# Extender.net
KiCad netlist of a schematic drawn in EAGLE
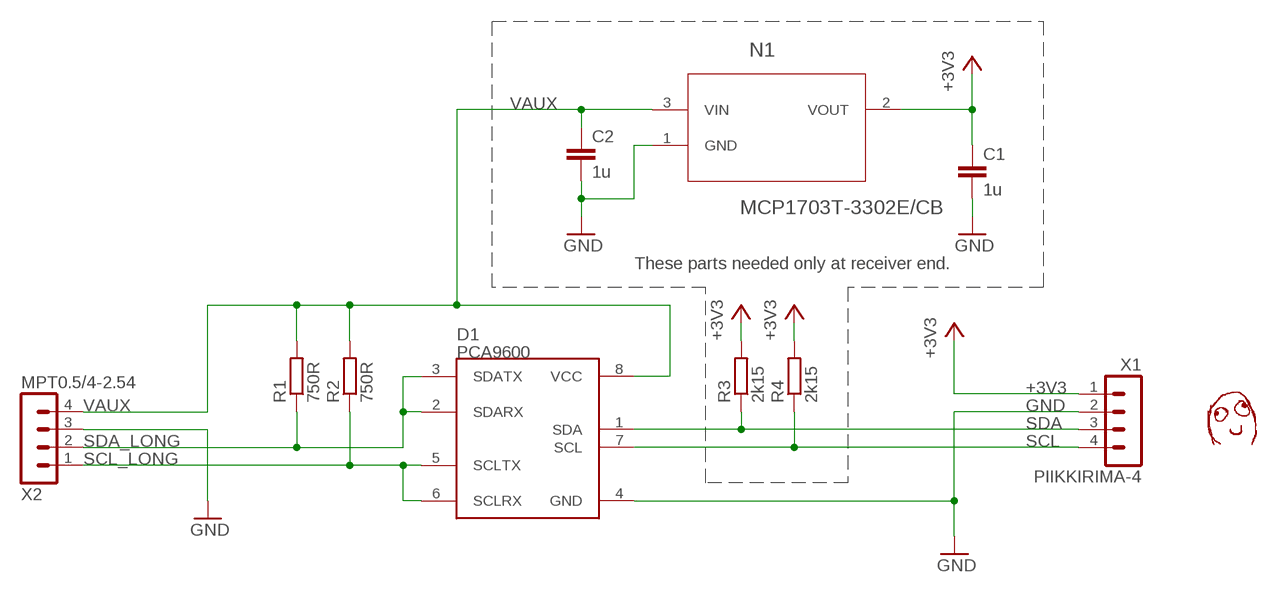
[diagram p0: schematic, sheet 1]

(export (version "E")
  (design (tool "Eeschema 10.0.6"))
  (components
    (comp (ref "C1")
      (value "1u")
      (footprint "eagle-import:C0805")
      (libsource (lib "eagle-import") (part "C-EUC0805"))
    )
    (comp (ref "C2")
      (value "1u")
      (footprint "eagle-import:C0805")
      (libsource (lib "eagle-import") (part "C-EUC0805"))
    )
    (comp (ref "D1")
      (value "PCA9600")
      (footprint "eagle-import:SOP65P490X110-8N")
      (libsource (lib "eagle-import") (part "PCA9600"))
    )
    (comp (ref "N1")
      (value "MCP1703T-3302E/CB")
      (footprint "eagle-import:SOT95P300X145-3N")
      (libsource (lib "eagle-import") (part "MCP1703T-3302E/CB"))
    )
    (comp (ref "R1")
      (value "750R")
      (footprint "eagle-import:R0603")
      (libsource (lib "eagle-import") (part "R-EU_R0603"))
    )
    (comp (ref "R2")
      (value "750R")
      (footprint "eagle-import:R0603")
      (libsource (lib "eagle-import") (part "R-EU_R0603"))
    )
    (comp (ref "R3")
      (value "2k15")
      (footprint "eagle-import:R0603")
      (libsource (lib "eagle-import") (part "R-EU_R0603"))
    )
    (comp (ref "R4")
      (value "2k15")
      (footprint "eagle-import:R0603")
      (libsource (lib "eagle-import") (part "R-EU_R0603"))
    )
    (comp (ref "U$1")
      (value "DAFUG")
      (footprint "eagle-import:DAFUG")
      (libsource (lib "eagle-import") (part "DAFUG"))
    )
    (comp (ref "X1")
      (value "PIIKKIRIMA-4")
      (footprint "eagle-import:PIIKKIRIMA-4")
      (libsource (lib "eagle-import") (part "PIIKKIRIMA-4"))
    )
    (comp (ref "X2")
      (value "MPT0.5/4-2.54")
      (footprint "eagle-import:MPT0.5_4-2.54")
      (libsource (lib "eagle-import") (part "MPT0.5/4-2.54"))
    )
  )
  (nets
    (net (code "1") (name "+3V3") (class "Default")
      (node (ref "C1") (pin "1") (pinfunction "1_1") (pintype "passive"))
      (node (ref "N1") (pin "2") (pinfunction "VOUT_2") (pintype "output"))
      (node (ref "R3") (pin "2") (pinfunction "2_2") (pintype "passive"))
      (node (ref "R4") (pin "2") (pinfunction "2_2") (pintype "passive"))
      (node (ref "X1") (pin "1") (pinfunction "1_1") (pintype "passive"))
    )
    (net (code "2") (name "/SCL") (class "Default")
      (node (ref "D1") (pin "7") (pinfunction "SCL_7") (pintype "bidirectional"))
      (node (ref "R4") (pin "1") (pinfunction "1_1") (pintype "passive"))
      (node (ref "X1") (pin "4") (pinfunction "4_4") (pintype "passive"))
    )
    (net (code "3") (name "/SCL_LONG") (class "Default")
      (node (ref "D1") (pin "5") (pinfunction "SCLTX_5") (pintype "bidirectional"))
      (node (ref "D1") (pin "6") (pinfunction "SCLRX_6") (pintype "bidirectional"))
      (node (ref "R2") (pin "1") (pinfunction "1_1") (pintype "passive"))
      (node (ref "X2") (pin "1") (pinfunction "1_1") (pintype "passive"))
    )
    (net (code "4") (name "/SDA") (class "Default")
      (node (ref "D1") (pin "1") (pinfunction "SDA_1") (pintype "bidirectional"))
      (node (ref "R3") (pin "1") (pinfunction "1_1") (pintype "passive"))
      (node (ref "X1") (pin "3") (pinfunction "3_3") (pintype "passive"))
    )
    (net (code "5") (name "/SDA_LONG") (class "Default")
      (node (ref "D1") (pin "2") (pinfunction "SDARX_2") (pintype "bidirectional"))
      (node (ref "D1") (pin "3") (pinfunction "SDATX_3") (pintype "bidirectional"))
      (node (ref "R1") (pin "1") (pinfunction "1_1") (pintype "passive"))
      (node (ref "X2") (pin "2") (pinfunction "2_2") (pintype "passive"))
    )
    (net (code "6") (name "/VAUX") (class "Default")
      (node (ref "C2") (pin "1") (pinfunction "1_1") (pintype "passive"))
      (node (ref "D1") (pin "8") (pinfunction "VCC_8") (pintype "bidirectional"))
      (node (ref "N1") (pin "3") (pinfunction "VIN_3") (pintype "input"))
      (node (ref "R1") (pin "2") (pinfunction "2_2") (pintype "passive"))
      (node (ref "R2") (pin "2") (pinfunction "2_2") (pintype "passive"))
      (node (ref "X2") (pin "4") (pinfunction "4_4") (pintype "passive"))
    )
    (net (code "7") (name "GND") (class "Default")
      (node (ref "C1") (pin "2") (pinfunction "2_2") (pintype "passive"))
      (node (ref "C2") (pin "2") (pinfunction "2_2") (pintype "passive"))
      (node (ref "D1") (pin "4") (pinfunction "GND_4") (pintype "bidirectional"))
      (node (ref "N1") (pin "1") (pinfunction "GND_1") (pintype "passive"))
      (node (ref "X1") (pin "2") (pinfunction "2_2") (pintype "passive"))
      (node (ref "X2") (pin "3") (pinfunction "3_3") (pintype "passive"))
    )
  )
)
